# STM32F401R.net
KiCad netlist of a schematic drawn in Altium Designer
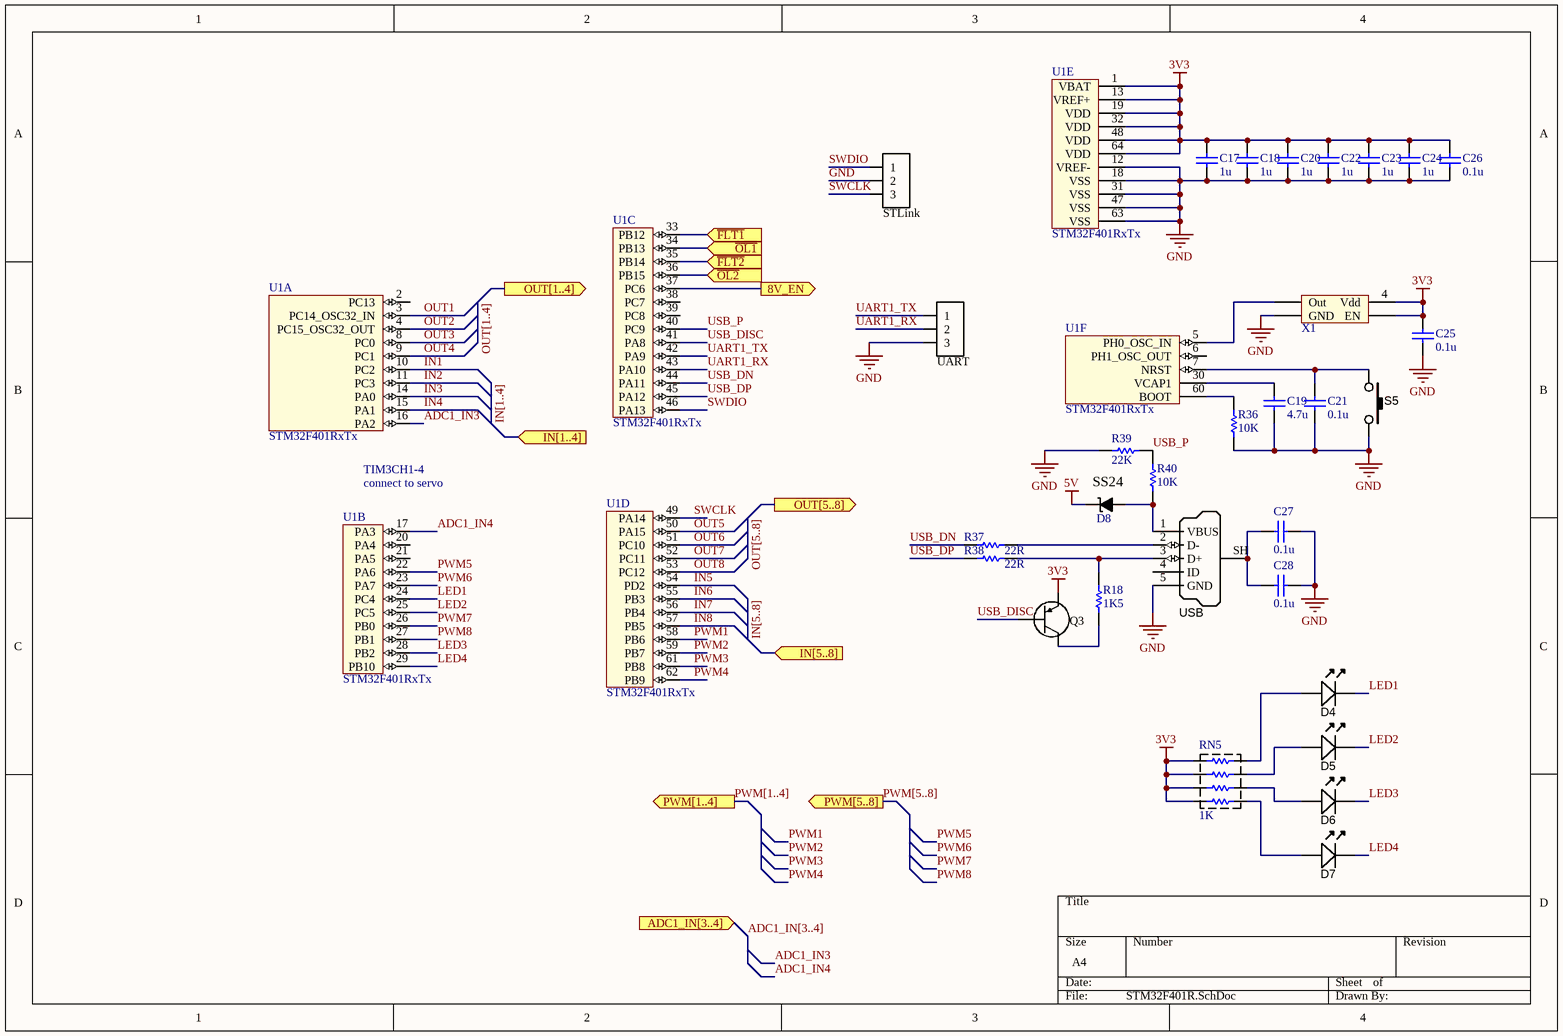
[diagram p0: STM32F401R.SchDoc]

(export (version "E")
  (design (tool "Eeschema 10.0.6"))
  (components
    (comp (ref "C17")
      (value "1u")
      (footprint "CAPC1608X90N")
      (description "Capacitor")
      (fields (field (name "Comment") "Cap") (field (name "PUBLISHER") "Altium Limited"))
      (libsource (lib "IOBoard_Low") (part "Cap"))
    )
    (comp (ref "C18")
      (value "1u")
      (footprint "CAPC1608X90N")
      (description "Capacitor")
      (fields (field (name "Comment") "Cap") (field (name "PUBLISHER") "Altium Limited"))
      (libsource (lib "IOBoard_Low") (part "Cap"))
    )
    (comp (ref "C19")
      (value "4.7u")
      (footprint "CAPC1608X90N")
      (description "Capacitor")
      (fields (field (name "Comment") "Cap") (field (name "PUBLISHER") "Altium Limited"))
      (libsource (lib "IOBoard_Low") (part "Cap"))
    )
    (comp (ref "C20")
      (value "1u")
      (footprint "CAPC1608X90N")
      (description "Capacitor")
      (fields (field (name "Comment") "Cap") (field (name "PUBLISHER") "Altium Limited"))
      (libsource (lib "IOBoard_Low") (part "Cap"))
    )
    (comp (ref "C21")
      (value "0.1u")
      (footprint "CAPC1608X90N")
      (description "Capacitor")
      (fields (field (name "Comment") "Cap") (field (name "PUBLISHER") "Altium Limited"))
      (libsource (lib "IOBoard_Low") (part "Cap"))
    )
    (comp (ref "C22")
      (value "1u")
      (footprint "CAPC1608X90N")
      (description "Capacitor")
      (fields (field (name "Comment") "Cap") (field (name "PUBLISHER") "Altium Limited"))
      (libsource (lib "IOBoard_Low") (part "Cap"))
    )
    (comp (ref "C23")
      (value "1u")
      (footprint "CAPC1608X90N")
      (description "Capacitor")
      (fields (field (name "Comment") "Cap") (field (name "PUBLISHER") "Altium Limited"))
      (libsource (lib "IOBoard_Low") (part "Cap"))
    )
    (comp (ref "C24")
      (value "1u")
      (footprint "CAPC1608X90N")
      (description "Capacitor")
      (fields (field (name "Comment") "Cap") (field (name "PUBLISHER") "Altium Limited"))
      (libsource (lib "IOBoard_Low") (part "Cap"))
    )
    (comp (ref "C25")
      (value "0.1u")
      (footprint "CAPC1608X90N")
      (description "Capacitor")
      (fields (field (name "Comment") "Cap") (field (name "PUBLISHER") "Altium Limited"))
      (libsource (lib "IOBoard_Low") (part "Cap"))
    )
    (comp (ref "C26")
      (value "0.1u")
      (footprint "CAPC1608X90N")
      (description "Capacitor")
      (fields (field (name "Comment") "Cap") (field (name "PUBLISHER") "Altium Limited"))
      (libsource (lib "IOBoard_Low") (part "Cap"))
    )
    (comp (ref "C27")
      (value "0.1u")
      (footprint "CAPC1608X90N")
      (description "Capacitor")
      (fields (field (name "Comment") "Cap") (field (name "PUBLISHER") "Altium Limited"))
      (libsource (lib "IOBoard_Low") (part "Cap"))
    )
    (comp (ref "C28")
      (value "0.1u")
      (footprint "CAPC1608X90N")
      (description "Capacitor")
      (fields (field (name "Comment") "Cap") (field (name "PUBLISHER") "Altium Limited"))
      (libsource (lib "IOBoard_Low") (part "Cap"))
    )
    (comp (ref "D4")
      (value "LED_Green_GullWing")
      (footprint "LED-0805-A")
      (description "LED Gull-wing SMD High-intensity Green 450mcd 574nm")
      (libsource (lib "IOBoard") (part "LED_Green_GullWing"))
    )
    (comp (ref "D5")
      (value "LED_Green_GullWing")
      (footprint "LED-0805-A")
      (description "LED Gull-wing SMD High-intensity Green 450mcd 574nm")
      (libsource (lib "IOBoard") (part "LED_Green_GullWing"))
    )
    (comp (ref "D6")
      (value "LED_Green_GullWing")
      (footprint "LED-0805-A")
      (description "LED Gull-wing SMD High-intensity Green 450mcd 574nm")
      (libsource (lib "IOBoard") (part "LED_Green_GullWing"))
    )
    (comp (ref "D7")
      (value "LED_Green_GullWing")
      (footprint "LED-0805-A")
      (description "LED Gull-wing SMD High-intensity Green 450mcd 574nm")
      (libsource (lib "IOBoard") (part "LED_Green_GullWing"))
    )
    (comp (ref "D8")
      (value "MBRA210LT3G")
      (footprint "SMA")
      (description "Surface Mount  Schottky Power Rectifier")
      (fields (field (name "MANUFACTURER") "ON semiconductor"))
      (libsource (lib "IOBoard_Low") (part "MBRA210LT3G"))
    )
    (comp (ref "Q3")
      (value "DTA114YYUA")
      (footprint "SOT323")
      (description "PNP -100mA -50V Digital Transistor (Bias Resistor Built-in Transistor)")
      (fields (field (name "MANUFACTURER") "ROHM"))
      (libsource (lib "IOBoard") (part "DTA114YYUA"))
    )
    (comp (ref "R18")
      (value "1K5")
      (footprint "RESC1608X55N")
      (description "Resistor")
      (fields (field (name "Comment") "Res1") (field (name "PUBLISHER") "Altium Limited"))
      (libsource (lib "IOBoard_Low") (part "Res1"))
    )
    (comp (ref "R36")
      (value "10K")
      (footprint "RESC1608X55N")
      (description "Resistor")
      (fields (field (name "Comment") "Res1") (field (name "PUBLISHER") "Altium Limited"))
      (libsource (lib "IOBoard_Low") (part "Res1"))
    )
    (comp (ref "R37")
      (value "22R")
      (footprint "RESC1608X55N")
      (description "Resistor")
      (fields (field (name "Comment") "Res1") (field (name "PUBLISHER") "Altium Limited"))
      (libsource (lib "IOBoard_Low") (part "Res1"))
    )
    (comp (ref "R38")
      (value "22R")
      (footprint "RESC1608X55N")
      (description "Resistor")
      (fields (field (name "Comment") "Res1") (field (name "PUBLISHER") "Altium Limited"))
      (libsource (lib "IOBoard_Low") (part "Res1"))
    )
    (comp (ref "R39")
      (value "22K")
      (footprint "RESC1608X55N")
      (description "Resistor")
      (fields (field (name "Comment") "Res1") (field (name "PUBLISHER") "Altium Limited"))
      (libsource (lib "IOBoard_Low") (part "Res1"))
    )
    (comp (ref "R40")
      (value "10K")
      (footprint "RESC1608X55N")
      (description "Resistor")
      (fields (field (name "Comment") "Res1") (field (name "PUBLISHER") "Altium Limited"))
      (libsource (lib "IOBoard_Low") (part "Res1"))
    )
    (comp (ref "RN5")
      (value "1K")
      (footprint "RESCAXS50P160X320X70-8N")
      (fields (field (name "Comment") "resistor network"))
      (libsource (lib "IOBoard") (part "RES_NET"))
    )
    (comp (ref "S5")
      (value "SW_THT_PB_4.3mm")
      (footprint "TACT_SWT-SMD-4.4")
      (description "Switch, tact, 4.3mm stem")
      (libsource (lib "IOBoard") (part "SW_THT_PB_4.3mm"))
    )
    (comp (ref "STLink")
      (value "Header")
      (footprint "1x3POS_HEADER")
      (description "Header 3-pin")
      (libsource (lib "IOBoard") (part "Header3P"))
    )
    (comp (ref "U1")
      (value "STM32F401RxTx")
      (footprint "LQFP64")
      (libsource (lib "IOBoard") (part "STM32F401RxTx"))
    )
    (comp (ref "UART")
      (value "Header")
      (footprint "1x3POS_HEADER")
      (description "Header 3-pin")
      (libsource (lib "IOBoard") (part "Header3P"))
    )
    (comp (ref "USB")
      (value "USB Micro Type B")
      (footprint "USB_MICRO-B")
      (description "Connector SMD USB Micro Type B middle mount")
      (libsource (lib "IOBoard") (part "USB_Micro_TypeB"))
    )
    (comp (ref "X1")
      (value "ASV-8.000MHZ-EJ-T")
      (footprint "ASV SERIES")
      (description "3.3Vdc HCMOS SMD Crystal Clock Oscillator")
      (fields (field (name "MANUFACTURER") "Abracon"))
      (libsource (lib "IOBoard") (part "ASV-8.000MHZ-EJ-T"))
    )
  )
  (nets
    (net (code "1") (name "/8V_EN") (class "Default")
      (node (ref "U1") (pin "37") (pinfunction "PC6_37") (pintype "bidirectional"))
    )
    (net (code "2") (name "/ADC1_IN3") (class "Default")
      (node (ref "U1") (pin "16") (pinfunction "PA2_16") (pintype "bidirectional"))
    )
    (net (code "3") (name "/ADC1_IN4") (class "Default")
      (node (ref "U1") (pin "17") (pinfunction "PA3_17") (pintype "bidirectional"))
    )
    (net (code "5") (name "/IN1") (class "Default")
      (node (ref "U1") (pin "10") (pinfunction "PC2_10") (pintype "bidirectional"))
    )
    (net (code "6") (name "/IN2") (class "Default")
      (node (ref "U1") (pin "11") (pinfunction "PC3_11") (pintype "bidirectional"))
    )
    (net (code "7") (name "/IN3") (class "Default")
      (node (ref "U1") (pin "14") (pinfunction "PA0_14") (pintype "bidirectional"))
    )
    (net (code "8") (name "/IN4") (class "Default")
      (node (ref "U1") (pin "15") (pinfunction "PA1_15") (pintype "bidirectional"))
    )
    (net (code "9") (name "/IN5") (class "Default")
      (node (ref "U1") (pin "54") (pinfunction "PD2_54") (pintype "bidirectional"))
    )
    (net (code "10") (name "/IN6") (class "Default")
      (node (ref "U1") (pin "55") (pinfunction "PB3_55") (pintype "bidirectional"))
    )
    (net (code "11") (name "/IN7") (class "Default")
      (node (ref "U1") (pin "56") (pinfunction "PB4_56") (pintype "bidirectional"))
    )
    (net (code "12") (name "/IN8") (class "Default")
      (node (ref "U1") (pin "57") (pinfunction "PB5_57") (pintype "bidirectional"))
    )
    (net (code "15") (name "/LED1") (class "Default")
      (node (ref "D4") (pin "K") (pinfunction "K_K") (pintype "passive"))
      (node (ref "U1") (pin "24") (pinfunction "PC4_24") (pintype "bidirectional"))
    )
    (net (code "16") (name "/LED2") (class "Default")
      (node (ref "D5") (pin "K") (pinfunction "K_K") (pintype "passive"))
      (node (ref "U1") (pin "25") (pinfunction "PC5_25") (pintype "bidirectional"))
    )
    (net (code "17") (name "/LED3") (class "Default")
      (node (ref "D6") (pin "K") (pinfunction "K_K") (pintype "passive"))
      (node (ref "U1") (pin "28") (pinfunction "PB2_28") (pintype "bidirectional"))
    )
    (net (code "18") (name "/LED4") (class "Default")
      (node (ref "D7") (pin "K") (pinfunction "K_K") (pintype "passive"))
      (node (ref "U1") (pin "29") (pinfunction "PB10_29") (pintype "bidirectional"))
    )
    (net (code "19") (name "/OUT1") (class "Default")
      (node (ref "U1") (pin "3") (pinfunction "PC14_OSC32_IN_3") (pintype "bidirectional"))
    )
    (net (code "20") (name "/OUT2") (class "Default")
      (node (ref "U1") (pin "4") (pinfunction "PC15_OSC32_OUT_4") (pintype "bidirectional"))
    )
    (net (code "21") (name "/OUT3") (class "Default")
      (node (ref "U1") (pin "8") (pinfunction "PC0_8") (pintype "bidirectional"))
    )
    (net (code "22") (name "/OUT4") (class "Default")
      (node (ref "U1") (pin "9") (pinfunction "PC1_9") (pintype "bidirectional"))
    )
    (net (code "23") (name "/OUT5") (class "Default")
      (node (ref "U1") (pin "50") (pinfunction "PA15_50") (pintype "bidirectional"))
    )
    (net (code "24") (name "/OUT6") (class "Default")
      (node (ref "U1") (pin "51") (pinfunction "PC10_51") (pintype "bidirectional"))
    )
    (net (code "25") (name "/OUT7") (class "Default")
      (node (ref "U1") (pin "52") (pinfunction "PC11_52") (pintype "bidirectional"))
    )
    (net (code "26") (name "/OUT8") (class "Default")
      (node (ref "U1") (pin "53") (pinfunction "PC12_53") (pintype "bidirectional"))
    )
    (net (code "29") (name "/PWM1") (class "Default")
      (node (ref "U1") (pin "58") (pinfunction "PB6_58") (pintype "bidirectional"))
    )
    (net (code "30") (name "/PWM2") (class "Default")
      (node (ref "U1") (pin "59") (pinfunction "PB7_59") (pintype "bidirectional"))
    )
    (net (code "31") (name "/PWM3") (class "Default")
      (node (ref "U1") (pin "61") (pinfunction "PB8_61") (pintype "bidirectional"))
    )
    (net (code "32") (name "/PWM4") (class "Default")
      (node (ref "U1") (pin "62") (pinfunction "PB9_62") (pintype "bidirectional"))
    )
    (net (code "33") (name "/PWM5") (class "Default")
      (node (ref "U1") (pin "22") (pinfunction "PA6_22") (pintype "bidirectional"))
    )
    (net (code "34") (name "/PWM6") (class "Default")
      (node (ref "U1") (pin "23") (pinfunction "PA7_23") (pintype "bidirectional"))
    )
    (net (code "35") (name "/PWM7") (class "Default")
      (node (ref "U1") (pin "26") (pinfunction "PB0_26") (pintype "bidirectional"))
    )
    (net (code "36") (name "/PWM8") (class "Default")
      (node (ref "U1") (pin "27") (pinfunction "PB1_27") (pintype "bidirectional"))
    )
    (net (code "39") (name "/SWCLK") (class "Default")
      (node (ref "STLink") (pin "3") (pinfunction "3_3") (pintype "passive"))
      (node (ref "U1") (pin "49") (pinfunction "PA14_49") (pintype "bidirectional"))
    )
    (net (code "40") (name "/SWDIO") (class "Default")
      (node (ref "STLink") (pin "1") (pinfunction "1_1") (pintype "passive"))
      (node (ref "U1") (pin "46") (pinfunction "PA13_46") (pintype "bidirectional"))
    )
    (net (code "41") (name "/UART1_RX") (class "Default")
      (node (ref "U1") (pin "43") (pinfunction "PA10_43") (pintype "bidirectional"))
      (node (ref "UART") (pin "2") (pinfunction "2_2") (pintype "passive"))
    )
    (net (code "42") (name "/UART1_TX") (class "Default")
      (node (ref "U1") (pin "42") (pinfunction "PA9_42") (pintype "bidirectional"))
      (node (ref "UART") (pin "1") (pinfunction "1_1") (pintype "passive"))
    )
    (net (code "43") (name "/USB_DISC") (class "Default")
      (node (ref "Q3") (pin "1") (pinfunction "B_1") (pintype "passive"))
      (node (ref "U1") (pin "41") (pinfunction "PA8_41") (pintype "bidirectional"))
    )
    (net (code "44") (name "/USB_DN") (class "Default")
      (node (ref "R37") (pin "1") (pinfunction "1_1") (pintype "passive"))
      (node (ref "U1") (pin "44") (pinfunction "PA11_44") (pintype "bidirectional"))
    )
    (net (code "45") (name "/USB_DP") (class "Default")
      (node (ref "R38") (pin "1") (pinfunction "1_1") (pintype "passive"))
      (node (ref "U1") (pin "45") (pinfunction "PA12_45") (pintype "bidirectional"))
    )
    (net (code "46") (name "/USB_P") (class "Default")
      (node (ref "R39") (pin "1") (pinfunction "1_1") (pintype "passive"))
      (node (ref "R40") (pin "2") (pinfunction "2_2") (pintype "passive"))
      (node (ref "U1") (pin "40") (pinfunction "PC9_40") (pintype "bidirectional"))
    )
    (net (code "47") (name "/~{FLT1}") (class "Default")
      (node (ref "U1") (pin "33") (pinfunction "PB12_33") (pintype "bidirectional"))
    )
    (net (code "48") (name "/~{FLT2}") (class "Default")
      (node (ref "U1") (pin "35") (pinfunction "PB14_35") (pintype "bidirectional"))
    )
    (net (code "49") (name "/~{OL1}") (class "Default")
      (node (ref "U1") (pin "34") (pinfunction "PB13_34") (pintype "bidirectional"))
    )
    (net (code "50") (name "/~{OL2}") (class "Default")
      (node (ref "U1") (pin "36") (pinfunction "PB15_36") (pintype "bidirectional"))
    )
    (net (code "51") (name "3V3") (class "Default")
      (node (ref "C17") (pin "2") (pinfunction "2_2") (pintype "passive"))
      (node (ref "C18") (pin "2") (pinfunction "2_2") (pintype "passive"))
      (node (ref "C20") (pin "2") (pinfunction "2_2") (pintype "passive"))
      (node (ref "C22") (pin "2") (pinfunction "2_2") (pintype "passive"))
      (node (ref "C23") (pin "2") (pinfunction "2_2") (pintype "passive"))
      (node (ref "C24") (pin "2") (pinfunction "2_2") (pintype "passive"))
      (node (ref "C25") (pin "2") (pinfunction "2_2") (pintype "passive"))
      (node (ref "C26") (pin "2") (pinfunction "2_2") (pintype "passive"))
      (node (ref "Q3") (pin "2") (pinfunction "E_2") (pintype "passive"))
      (node (ref "RN5") (pin "1") (pinfunction "1_1") (pintype "power_in"))
      (node (ref "RN5") (pin "2") (pinfunction "2_2") (pintype "power_in"))
      (node (ref "RN5") (pin "3") (pinfunction "3_3") (pintype "power_in"))
      (node (ref "RN5") (pin "4") (pinfunction "4_4") (pintype "power_in"))
      (node (ref "U1") (pin "1") (pinfunction "VBAT_1") (pintype "power_in"))
      (node (ref "U1") (pin "13") (pinfunction "VREF+_13") (pintype "power_in"))
      (node (ref "U1") (pin "19") (pinfunction "VDD_19") (pintype "power_in"))
      (node (ref "U1") (pin "32") (pinfunction "VDD_32") (pintype "power_in"))
      (node (ref "U1") (pin "48") (pinfunction "VDD_48") (pintype "power_in"))
      (node (ref "U1") (pin "64") (pinfunction "VDD_64") (pintype "power_in"))
      (node (ref "X1") (pin "1") (pinfunction "EN_1") (pintype "passive"))
      (node (ref "X1") (pin "4") (pinfunction "Vdd_4") (pintype "passive"))
    )
    (net (code "52") (name "5V") (class "Default")
      (node (ref "D8") (pin "K") (pinfunction "Cathode_K") (pintype "passive"))
    )
    (net (code "53") (name "GND") (class "Default")
      (node (ref "C17") (pin "1") (pinfunction "1_1") (pintype "passive"))
      (node (ref "C18") (pin "1") (pinfunction "1_1") (pintype "passive"))
      (node (ref "C19") (pin "1") (pinfunction "1_1") (pintype "passive"))
      (node (ref "C20") (pin "1") (pinfunction "1_1") (pintype "passive"))
      (node (ref "C21") (pin "1") (pinfunction "1_1") (pintype "passive"))
      (node (ref "C22") (pin "1") (pinfunction "1_1") (pintype "passive"))
      (node (ref "C23") (pin "1") (pinfunction "1_1") (pintype "passive"))
      (node (ref "C24") (pin "1") (pinfunction "1_1") (pintype "passive"))
      (node (ref "C25") (pin "1") (pinfunction "1_1") (pintype "passive"))
      (node (ref "C26") (pin "1") (pinfunction "1_1") (pintype "passive"))
      (node (ref "C27") (pin "2") (pinfunction "2_2") (pintype "passive"))
      (node (ref "C28") (pin "2") (pinfunction "2_2") (pintype "passive"))
      (node (ref "R36") (pin "1") (pinfunction "1_1") (pintype "passive"))
      (node (ref "R39") (pin "2") (pinfunction "2_2") (pintype "passive"))
      (node (ref "S5") (pin "2") (pintype "passive"))
      (node (ref "STLink") (pin "2") (pinfunction "2_2") (pintype "passive"))
      (node (ref "U1") (pin "12") (pinfunction "VREF-_12") (pintype "power_in"))
      (node (ref "U1") (pin "18") (pinfunction "VSS_18") (pintype "power_in"))
      (node (ref "U1") (pin "31") (pinfunction "VSS_31") (pintype "power_in"))
      (node (ref "U1") (pin "47") (pinfunction "VSS_47") (pintype "power_in"))
      (node (ref "U1") (pin "63") (pinfunction "VSS_63") (pintype "power_in"))
      (node (ref "UART") (pin "3") (pinfunction "3_3") (pintype "passive"))
      (node (ref "USB") (pin "5") (pinfunction "GND_5") (pintype "power_in"))
      (node (ref "X1") (pin "2") (pinfunction "GND_2") (pintype "passive"))
    )
    (net (code "54") (name "Net-(D4-PadA)") (class "Default")
      (node (ref "D4") (pin "A") (pinfunction "A_A") (pintype "passive"))
      (node (ref "RN5") (pin "8") (pinfunction "8_8") (pintype "power_in"))
    )
    (net (code "55") (name "Net-(D5-PadA)") (class "Default")
      (node (ref "D5") (pin "A") (pinfunction "A_A") (pintype "passive"))
      (node (ref "RN5") (pin "7") (pinfunction "7_7") (pintype "power_in"))
    )
    (net (code "56") (name "Net-(D6-PadA)") (class "Default")
      (node (ref "D6") (pin "A") (pinfunction "A_A") (pintype "passive"))
      (node (ref "RN5") (pin "6") (pinfunction "6_6") (pintype "power_in"))
    )
    (net (code "57") (name "Net-(D7-PadA)") (class "Default")
      (node (ref "D7") (pin "A") (pinfunction "A_A") (pintype "passive"))
      (node (ref "RN5") (pin "5") (pinfunction "5_5") (pintype "power_in"))
    )
    (net (code "58") (name "Net-(D8-Anode)") (class "Default")
      (node (ref "D8") (pin "A") (pinfunction "Anode_A") (pintype "passive"))
      (node (ref "R40") (pin "1") (pinfunction "1_1") (pintype "passive"))
      (node (ref "USB") (pin "1") (pinfunction "VBUS_1") (pintype "power_in"))
    )
    (net (code "59") (name "Net-(Q3-C)") (class "Default")
      (node (ref "Q3") (pin "3") (pinfunction "C_3") (pintype "passive"))
      (node (ref "R18") (pin "1") (pinfunction "1_1") (pintype "passive"))
    )
    (net (code "60") (name "Net-(U1F-BOOT)") (class "Default")
      (node (ref "R36") (pin "2") (pinfunction "2_2") (pintype "passive"))
      (node (ref "U1") (pin "60") (pinfunction "BOOT_60") (pintype "power_in"))
    )
    (net (code "61") (name "Net-(U1F-NRST)") (class "Default")
      (node (ref "C21") (pin "2") (pinfunction "2_2") (pintype "passive"))
      (node (ref "S5") (pin "1") (pintype "passive"))
      (node (ref "U1") (pin "7") (pinfunction "NRST_7") (pintype "bidirectional"))
    )
    (net (code "62") (name "Net-(U1F-PH0_OSC_IN)") (class "Default")
      (node (ref "U1") (pin "5") (pinfunction "PH0_OSC_IN_5") (pintype "bidirectional"))
      (node (ref "X1") (pin "3") (pinfunction "Out_3") (pintype "passive"))
    )
    (net (code "63") (name "Net-(U1F-VCAP1)") (class "Default")
      (node (ref "C19") (pin "2") (pinfunction "2_2") (pintype "passive"))
      (node (ref "U1") (pin "30") (pinfunction "VCAP1_30") (pintype "power_in"))
    )
    (net (code "64") (name "Net-(USB-D+)") (class "Default")
      (node (ref "R18") (pin "2") (pinfunction "2_2") (pintype "passive"))
      (node (ref "R38") (pin "2") (pinfunction "2_2") (pintype "passive"))
      (node (ref "USB") (pin "3") (pinfunction "D+_3") (pintype "bidirectional"))
    )
    (net (code "65") (name "Net-(USB-D-)") (class "Default")
      (node (ref "R37") (pin "2") (pinfunction "2_2") (pintype "passive"))
      (node (ref "USB") (pin "2") (pinfunction "D-_2") (pintype "bidirectional"))
    )
    (net (code "66") (name "Net-(USB-Shell)") (class "Default")
      (node (ref "C27") (pin "1") (pinfunction "1_1") (pintype "passive"))
      (node (ref "C28") (pin "1") (pinfunction "1_1") (pintype "passive"))
      (node (ref "USB") (pin "SH") (pinfunction "Shell_SH") (pintype "passive"))
    )
    (net (code "67") (name "unconnected-(U1A-PC13-Pad2)") (class "Default")
      (node (ref "U1") (pin "2") (pinfunction "PC13_2") (pintype "bidirectional"))
    )
    (net (code "68") (name "unconnected-(U1B-PA4-Pad20)") (class "Default")
      (node (ref "U1") (pin "20") (pinfunction "PA4_20") (pintype "bidirectional"))
    )
    (net (code "69") (name "unconnected-(U1B-PA5-Pad21)") (class "Default")
      (node (ref "U1") (pin "21") (pinfunction "PA5_21") (pintype "bidirectional"))
    )
    (net (code "70") (name "unconnected-(U1C-PC7-Pad38)") (class "Default")
      (node (ref "U1") (pin "38") (pinfunction "PC7_38") (pintype "bidirectional"))
    )
    (net (code "71") (name "unconnected-(U1C-PC8-Pad39)") (class "Default")
      (node (ref "U1") (pin "39") (pinfunction "PC8_39") (pintype "bidirectional"))
    )
    (net (code "72") (name "unconnected-(U1F-PH1_OSC_OUT-Pad6)") (class "Default")
      (node (ref "U1") (pin "6") (pinfunction "PH1_OSC_OUT_6") (pintype "bidirectional"))
    )
    (net (code "73") (name "unconnected-(USB-ID-Pad4)") (class "Default")
      (node (ref "USB") (pin "4") (pinfunction "ID_4") (pintype "passive"))
    )
  )
)
